# PMS.net
KiCad netlist of a schematic drawn in Altium Designer
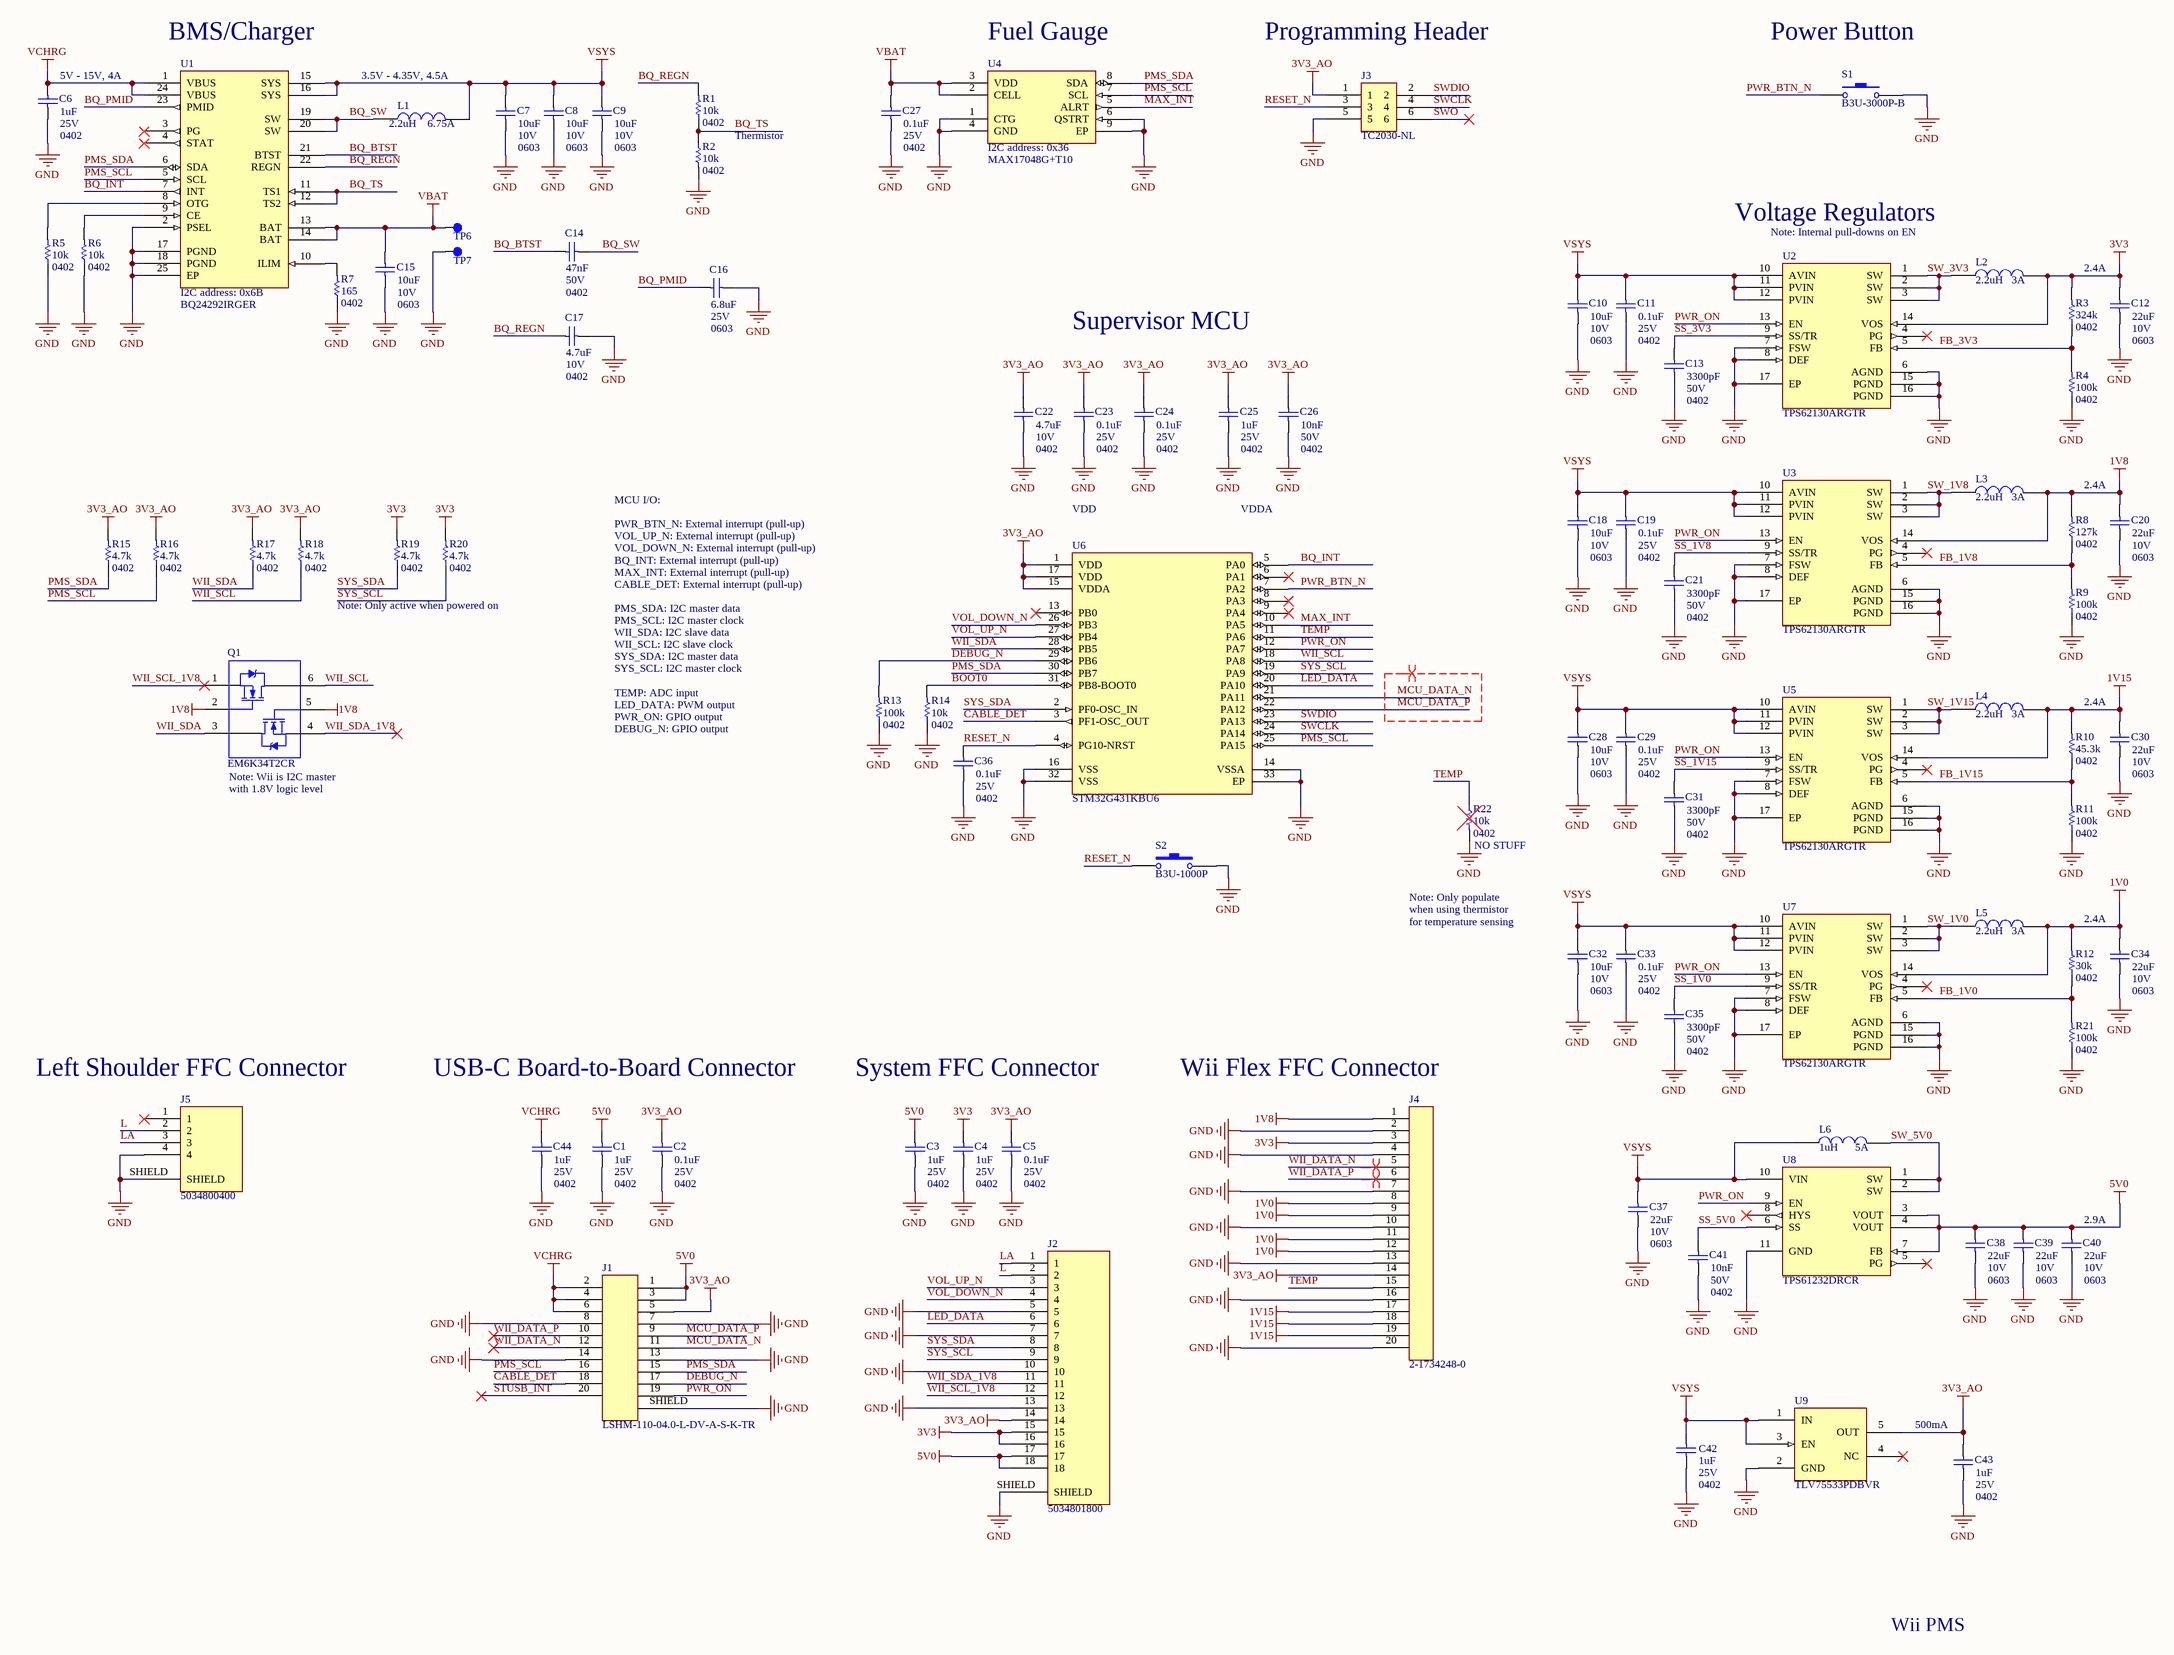
[diagram p0: PMS.SchDoc]

(export (version "E")
  (design (tool "Eeschema 10.0.6"))
  (components
    (comp (ref "C1")
      (value "1uF")
      (footprint "CAPC1005X06N")
      (description "General purpose capacitor")
      (fields
        (field (name "RATED VOLTAGE") "25V")
        (field (name "PACKAGE") "0402")
        (field (name "Comment") "Capacitor")
      )
      (libsource (lib "Schematic_Generic") (part "Capacitor"))
    )
    (comp (ref "C2")
      (value "0.1uF")
      (footprint "CAPC1005X06N")
      (description "General purpose capacitor")
      (fields
        (field (name "RATED VOLTAGE") "25V")
        (field (name "PACKAGE") "0402")
        (field (name "Comment") "Capacitor")
      )
      (libsource (lib "Schematic_Generic") (part "Capacitor"))
    )
    (comp (ref "C3")
      (value "1uF")
      (footprint "CAPC1005X06N")
      (description "General purpose capacitor")
      (fields
        (field (name "RATED VOLTAGE") "25V")
        (field (name "PACKAGE") "0402")
        (field (name "Comment") "Capacitor")
      )
      (libsource (lib "Schematic_Generic") (part "Capacitor"))
    )
    (comp (ref "C4")
      (value "1uF")
      (footprint "CAPC1005X06N")
      (description "General purpose capacitor")
      (fields
        (field (name "RATED VOLTAGE") "25V")
        (field (name "PACKAGE") "0402")
        (field (name "Comment") "Capacitor")
      )
      (libsource (lib "Schematic_Generic") (part "Capacitor"))
    )
    (comp (ref "C5")
      (value "0.1uF")
      (footprint "CAPC1005X06N")
      (description "General purpose capacitor")
      (fields
        (field (name "RATED VOLTAGE") "25V")
        (field (name "PACKAGE") "0402")
        (field (name "Comment") "Capacitor")
      )
      (libsource (lib "Schematic_Generic") (part "Capacitor"))
    )
    (comp (ref "C6")
      (value "1uF")
      (footprint "CAPC1005X06N")
      (description "General purpose capacitor")
      (fields
        (field (name "RATED VOLTAGE") "25V")
        (field (name "PACKAGE") "0402")
        (field (name "Comment") "Capacitor")
      )
      (libsource (lib "Schematic_Generic") (part "Capacitor"))
    )
    (comp (ref "C7")
      (value "10uF")
      (footprint "CAPC1608X09N")
      (description "General purpose capacitor")
      (fields
        (field (name "RATED VOLTAGE") "10V")
        (field (name "PACKAGE") "0603")
        (field (name "Comment") "Capacitor")
      )
      (libsource (lib "Schematic_Generic") (part "Capacitor"))
    )
    (comp (ref "C8")
      (value "10uF")
      (footprint "CAPC1608X09N")
      (description "General purpose capacitor")
      (fields
        (field (name "RATED VOLTAGE") "10V")
        (field (name "PACKAGE") "0603")
        (field (name "Comment") "Capacitor")
      )
      (libsource (lib "Schematic_Generic") (part "Capacitor"))
    )
    (comp (ref "C9")
      (value "10uF")
      (footprint "CAPC1608X09N")
      (description "General purpose capacitor")
      (fields
        (field (name "RATED VOLTAGE") "10V")
        (field (name "PACKAGE") "0603")
        (field (name "Comment") "Capacitor")
      )
      (libsource (lib "Schematic_Generic") (part "Capacitor"))
    )
    (comp (ref "C10")
      (value "10uF")
      (footprint "CAPC1608X09N")
      (description "General purpose capacitor")
      (fields
        (field (name "RATED VOLTAGE") "10V")
        (field (name "PACKAGE") "0603")
        (field (name "Comment") "Capacitor")
      )
      (libsource (lib "Schematic_Generic") (part "Capacitor"))
    )
    (comp (ref "C11")
      (value "0.1uF")
      (footprint "CAPC1005X06N")
      (description "General purpose capacitor")
      (fields
        (field (name "RATED VOLTAGE") "25V")
        (field (name "PACKAGE") "0402")
        (field (name "Comment") "Capacitor")
      )
      (libsource (lib "Schematic_Generic") (part "Capacitor"))
    )
    (comp (ref "C12")
      (value "22uF")
      (footprint "CAPC1608X09N")
      (description "General purpose capacitor")
      (fields
        (field (name "RATED VOLTAGE") "10V")
        (field (name "PACKAGE") "0603")
        (field (name "Comment") "Capacitor")
      )
      (libsource (lib "Schematic_Generic") (part "Capacitor"))
    )
    (comp (ref "C13")
      (value "3300pF")
      (footprint "CAPC1005X06N")
      (description "General purpose capacitor")
      (fields
        (field (name "RATED VOLTAGE") "50V")
        (field (name "PACKAGE") "0402")
        (field (name "Comment") "Capacitor")
      )
      (libsource (lib "Schematic_Generic") (part "Capacitor"))
    )
    (comp (ref "C14")
      (value "47nF")
      (footprint "CAPC1005X06N")
      (description "General purpose capacitor")
      (fields
        (field (name "RATED VOLTAGE") "50V")
        (field (name "PACKAGE") "0402")
        (field (name "Comment") "Capacitor")
      )
      (libsource (lib "Schematic_Generic") (part "Capacitor"))
    )
    (comp (ref "C15")
      (value "10uF")
      (footprint "CAPC1608X09N")
      (description "General purpose capacitor")
      (fields
        (field (name "RATED VOLTAGE") "10V")
        (field (name "PACKAGE") "0603")
        (field (name "Comment") "Capacitor")
      )
      (libsource (lib "Schematic_Generic") (part "Capacitor"))
    )
    (comp (ref "C16")
      (value "6.8uF")
      (footprint "CAPC1608X09N")
      (description "General purpose capacitor")
      (fields
        (field (name "RATED VOLTAGE") "25V")
        (field (name "PACKAGE") "0603")
        (field (name "Comment") "Capacitor")
      )
      (libsource (lib "Schematic_Generic") (part "Capacitor"))
    )
    (comp (ref "C17")
      (value "4.7uF")
      (footprint "CAPC1005X06N")
      (description "General purpose capacitor")
      (fields
        (field (name "RATED VOLTAGE") "10V")
        (field (name "PACKAGE") "0402")
        (field (name "Comment") "Capacitor")
      )
      (libsource (lib "Schematic_Generic") (part "Capacitor"))
    )
    (comp (ref "C18")
      (value "10uF")
      (footprint "CAPC1608X09N")
      (description "General purpose capacitor")
      (fields
        (field (name "RATED VOLTAGE") "10V")
        (field (name "PACKAGE") "0603")
        (field (name "Comment") "Capacitor")
      )
      (libsource (lib "Schematic_Generic") (part "Capacitor"))
    )
    (comp (ref "C19")
      (value "0.1uF")
      (footprint "CAPC1005X06N")
      (description "General purpose capacitor")
      (fields
        (field (name "RATED VOLTAGE") "25V")
        (field (name "PACKAGE") "0402")
        (field (name "Comment") "Capacitor")
      )
      (libsource (lib "Schematic_Generic") (part "Capacitor"))
    )
    (comp (ref "C20")
      (value "22uF")
      (footprint "CAPC1608X09N")
      (description "General purpose capacitor")
      (fields
        (field (name "RATED VOLTAGE") "10V")
        (field (name "PACKAGE") "0603")
        (field (name "Comment") "Capacitor")
      )
      (libsource (lib "Schematic_Generic") (part "Capacitor"))
    )
    (comp (ref "C21")
      (value "3300pF")
      (footprint "CAPC1005X06N")
      (description "General purpose capacitor")
      (fields
        (field (name "RATED VOLTAGE") "50V")
        (field (name "PACKAGE") "0402")
        (field (name "Comment") "Capacitor")
      )
      (libsource (lib "Schematic_Generic") (part "Capacitor"))
    )
    (comp (ref "C22")
      (value "4.7uF")
      (footprint "CAPC1005X06N")
      (description "General purpose capacitor")
      (fields
        (field (name "RATED VOLTAGE") "10V")
        (field (name "PACKAGE") "0402")
        (field (name "Comment") "Capacitor")
      )
      (libsource (lib "Schematic_Generic") (part "Capacitor"))
    )
    (comp (ref "C23")
      (value "0.1uF")
      (footprint "CAPC1005X06N")
      (description "General purpose capacitor")
      (fields
        (field (name "RATED VOLTAGE") "25V")
        (field (name "PACKAGE") "0402")
        (field (name "Comment") "Capacitor")
      )
      (libsource (lib "Schematic_Generic") (part "Capacitor"))
    )
    (comp (ref "C24")
      (value "0.1uF")
      (footprint "CAPC1005X06N")
      (description "General purpose capacitor")
      (fields
        (field (name "RATED VOLTAGE") "25V")
        (field (name "PACKAGE") "0402")
        (field (name "Comment") "Capacitor")
      )
      (libsource (lib "Schematic_Generic") (part "Capacitor"))
    )
    (comp (ref "C25")
      (value "1uF")
      (footprint "CAPC1005X06N")
      (description "General purpose capacitor")
      (fields
        (field (name "RATED VOLTAGE") "25V")
        (field (name "PACKAGE") "0402")
        (field (name "Comment") "Capacitor")
      )
      (libsource (lib "Schematic_Generic") (part "Capacitor"))
    )
    (comp (ref "C26")
      (value "10nF")
      (footprint "CAPC1005X06N")
      (description "General purpose capacitor")
      (fields
        (field (name "RATED VOLTAGE") "50V")
        (field (name "PACKAGE") "0402")
        (field (name "Comment") "Capacitor")
      )
      (libsource (lib "Schematic_Generic") (part "Capacitor"))
    )
    (comp (ref "C27")
      (value "0.1uF")
      (footprint "CAPC1005X06N")
      (description "General purpose capacitor")
      (fields
        (field (name "RATED VOLTAGE") "25V")
        (field (name "PACKAGE") "0402")
        (field (name "Comment") "Capacitor")
      )
      (libsource (lib "Schematic_Generic") (part "Capacitor"))
    )
    (comp (ref "C28")
      (value "10uF")
      (footprint "CAPC1608X09N")
      (description "General purpose capacitor")
      (fields
        (field (name "RATED VOLTAGE") "10V")
        (field (name "PACKAGE") "0603")
        (field (name "Comment") "Capacitor")
      )
      (libsource (lib "Schematic_Generic") (part "Capacitor"))
    )
    (comp (ref "C29")
      (value "0.1uF")
      (footprint "CAPC1005X06N")
      (description "General purpose capacitor")
      (fields
        (field (name "RATED VOLTAGE") "25V")
        (field (name "PACKAGE") "0402")
        (field (name "Comment") "Capacitor")
      )
      (libsource (lib "Schematic_Generic") (part "Capacitor"))
    )
    (comp (ref "C30")
      (value "22uF")
      (footprint "CAPC1608X09N")
      (description "General purpose capacitor")
      (fields
        (field (name "RATED VOLTAGE") "10V")
        (field (name "PACKAGE") "0603")
        (field (name "Comment") "Capacitor")
      )
      (libsource (lib "Schematic_Generic") (part "Capacitor"))
    )
    (comp (ref "C31")
      (value "3300pF")
      (footprint "CAPC1005X06N")
      (description "General purpose capacitor")
      (fields
        (field (name "RATED VOLTAGE") "50V")
        (field (name "PACKAGE") "0402")
        (field (name "Comment") "Capacitor")
      )
      (libsource (lib "Schematic_Generic") (part "Capacitor"))
    )
    (comp (ref "C32")
      (value "10uF")
      (footprint "CAPC1608X09N")
      (description "General purpose capacitor")
      (fields
        (field (name "RATED VOLTAGE") "10V")
        (field (name "PACKAGE") "0603")
        (field (name "Comment") "Capacitor")
      )
      (libsource (lib "Schematic_Generic") (part "Capacitor"))
    )
    (comp (ref "C33")
      (value "0.1uF")
      (footprint "CAPC1005X06N")
      (description "General purpose capacitor")
      (fields
        (field (name "RATED VOLTAGE") "25V")
        (field (name "PACKAGE") "0402")
        (field (name "Comment") "Capacitor")
      )
      (libsource (lib "Schematic_Generic") (part "Capacitor"))
    )
    (comp (ref "C34")
      (value "22uF")
      (footprint "CAPC1608X09N")
      (description "General purpose capacitor")
      (fields
        (field (name "RATED VOLTAGE") "10V")
        (field (name "PACKAGE") "0603")
        (field (name "Comment") "Capacitor")
      )
      (libsource (lib "Schematic_Generic") (part "Capacitor"))
    )
    (comp (ref "C35")
      (value "3300pF")
      (footprint "CAPC1005X06N")
      (description "General purpose capacitor")
      (fields
        (field (name "RATED VOLTAGE") "50V")
        (field (name "PACKAGE") "0402")
        (field (name "Comment") "Capacitor")
      )
      (libsource (lib "Schematic_Generic") (part "Capacitor"))
    )
    (comp (ref "C36")
      (value "0.1uF")
      (footprint "CAPC1005X06N")
      (description "General purpose capacitor")
      (fields
        (field (name "RATED VOLTAGE") "25V")
        (field (name "PACKAGE") "0402")
        (field (name "Comment") "Capacitor")
      )
      (libsource (lib "Schematic_Generic") (part "Capacitor"))
    )
    (comp (ref "C37")
      (value "22uF")
      (footprint "CAPC1608X09N")
      (description "General purpose capacitor")
      (fields
        (field (name "RATED VOLTAGE") "10V")
        (field (name "PACKAGE") "0603")
        (field (name "Comment") "Capacitor")
      )
      (libsource (lib "Schematic_Generic") (part "Capacitor"))
    )
    (comp (ref "C38")
      (value "22uF")
      (footprint "CAPC1608X09N")
      (description "General purpose capacitor")
      (fields
        (field (name "RATED VOLTAGE") "10V")
        (field (name "PACKAGE") "0603")
        (field (name "Comment") "Capacitor")
      )
      (libsource (lib "Schematic_Generic") (part "Capacitor"))
    )
    (comp (ref "C39")
      (value "22uF")
      (footprint "CAPC1608X09N")
      (description "General purpose capacitor")
      (fields
        (field (name "RATED VOLTAGE") "10V")
        (field (name "PACKAGE") "0603")
        (field (name "Comment") "Capacitor")
      )
      (libsource (lib "Schematic_Generic") (part "Capacitor"))
    )
    (comp (ref "C40")
      (value "22uF")
      (footprint "CAPC1608X09N")
      (description "General purpose capacitor")
      (fields
        (field (name "RATED VOLTAGE") "10V")
        (field (name "PACKAGE") "0603")
        (field (name "Comment") "Capacitor")
      )
      (libsource (lib "Schematic_Generic") (part "Capacitor"))
    )
    (comp (ref "C41")
      (value "10nF")
      (footprint "CAPC1005X06N")
      (description "General purpose capacitor")
      (fields
        (field (name "RATED VOLTAGE") "50V")
        (field (name "PACKAGE") "0402")
        (field (name "Comment") "Capacitor")
      )
      (libsource (lib "Schematic_Generic") (part "Capacitor"))
    )
    (comp (ref "C42")
      (value "1uF")
      (footprint "CAPC1005X06N")
      (description "General purpose capacitor")
      (fields
        (field (name "RATED VOLTAGE") "25V")
        (field (name "PACKAGE") "0402")
        (field (name "Comment") "Capacitor")
      )
      (libsource (lib "Schematic_Generic") (part "Capacitor"))
    )
    (comp (ref "C43")
      (value "1uF")
      (footprint "CAPC1005X06N")
      (description "General purpose capacitor")
      (fields
        (field (name "RATED VOLTAGE") "25V")
        (field (name "PACKAGE") "0402")
        (field (name "Comment") "Capacitor")
      )
      (libsource (lib "Schematic_Generic") (part "Capacitor"))
    )
    (comp (ref "C44")
      (value "1uF")
      (footprint "CAPC1005X06N")
      (description "General purpose capacitor")
      (fields
        (field (name "RATED VOLTAGE") "25V")
        (field (name "PACKAGE") "0402")
        (field (name "Comment") "Capacitor")
      )
      (libsource (lib "Schematic_Generic") (part "Capacitor"))
    )
    (comp (ref "J1")
      (value "LSHM-110-04.0-L-DV-A-S-K-TR")
      (footprint "Footprint_Connector:LSHM-110-04.0-L-DV-A-S")
      (description "HERMAPHRODITIC 0.50MM SMD 20POS 4MM")
      (fields (field (name "MANUFACTURER") "Samtec"))
      (libsource (lib "Schematic_Connector") (part "LSHM-110-04.0-L-DV-A-S-K-TR"))
    )
    (comp (ref "J2")
      (value "5034801800")
      (footprint "Footprint_Connector:5034801800")
      (description "CONN FFC FPC 18POS 0.50MM R/A")
      (fields (field (name "MANUFACTURER") "Molex"))
      (libsource (lib "Schematic_Connector") (part "5034801800"))
    )
    (comp (ref "J3")
      (value "TC2030-NL")
      (footprint "Footprint_Connector:TC2030-NL")
      (description "6-Pin No-Legs Tag-Connect Plug-of-Nails™ Cable with Ribbon Connector")
      (libsource (lib "Schematic_Connector") (part "TC2030-NL"))
    )
    (comp (ref "J4")
      (value "2-1734248-0")
      (footprint "Footprint_Connector:2-1734248-0")
      (description "FFC/FPC CONNECTOR, RECEPTACLE 20POS 1ROW")
      (fields (field (name "MANUFACTURER") "TE Connectivity"))
      (libsource (lib "Schematic_Connector") (part "2-1734248-0"))
    )
    (comp (ref "J5")
      (value "5034800400")
      (footprint "Footprint_Connector:5034800400")
      (description "CONN FFC FPC 4POS 0.50MM R/A")
      (fields (field (name "MANUFACTURER") "Molex"))
      (libsource (lib "Schematic_Connector") (part "5034800400"))
    )
    (comp (ref "L1")
      (value "IHLP2020CZER2R2M11")
      (footprint "Footprint_Inductor:INDM5252X30N")
      (description "FIXED IND 2.2UH 6.75A 25 MOHM")
      (fields
        (field (name "MANUFACTURER") "Vishay Dale")
        (field (name "TOLERANCE") "20%")
        (field (name "CURRENT RATING") "6.75A")
        (field (name "INDUCTANCE") "2.2uH")
      )
      (libsource (lib "Schematic_Inductor") (part "IHLP2020CZER2R2M11"))
    )
    (comp (ref "L2")
      (value "IHLP1212BZER2R2M11")
      (footprint "Footprint_Inductor:INDM3030X20N")
      (description "FIXED IND 2.2UH 3A 46 MOHM SMD")
      (fields
        (field (name "MANUFACTURER") "Vishay Dale")
        (field (name "TOLERANCE") "20%")
        (field (name "CURRENT RATING") "3A")
        (field (name "INDUCTANCE") "2.2uH")
      )
      (libsource (lib "Schematic_Inductor") (part "IHLP1212BZER2R2M11"))
    )
    (comp (ref "L3")
      (value "IHLP1212BZER2R2M11")
      (footprint "Footprint_Inductor:INDM3030X20N")
      (description "FIXED IND 2.2UH 3A 46 MOHM SMD")
      (fields
        (field (name "MANUFACTURER") "Vishay Dale")
        (field (name "TOLERANCE") "20%")
        (field (name "CURRENT RATING") "3A")
        (field (name "INDUCTANCE") "2.2uH")
      )
      (libsource (lib "Schematic_Inductor") (part "IHLP1212BZER2R2M11"))
    )
    (comp (ref "L4")
      (value "IHLP1212BZER2R2M11")
      (footprint "Footprint_Inductor:INDM3030X20N")
      (description "FIXED IND 2.2UH 3A 46 MOHM SMD")
      (fields
        (field (name "MANUFACTURER") "Vishay Dale")
        (field (name "TOLERANCE") "20%")
        (field (name "CURRENT RATING") "3A")
        (field (name "INDUCTANCE") "2.2uH")
      )
      (libsource (lib "Schematic_Inductor") (part "IHLP1212BZER2R2M11"))
    )
    (comp (ref "L5")
      (value "IHLP1212BZER2R2M11")
      (footprint "Footprint_Inductor:INDM3030X20N")
      (description "FIXED IND 2.2UH 3A 46 MOHM SMD")
      (fields
        (field (name "MANUFACTURER") "Vishay Dale")
        (field (name "TOLERANCE") "20%")
        (field (name "CURRENT RATING") "3A")
        (field (name "INDUCTANCE") "2.2uH")
      )
      (libsource (lib "Schematic_Inductor") (part "IHLP1212BZER2R2M11"))
    )
    (comp (ref "L6")
      (value "IHLP1212BZER1R0M11")
      (footprint "Footprint_Inductor:INDM3030X20N")
      (description "FIXED IND 1UH 5A 24 MOHM SMD")
      (fields
        (field (name "MANUFACTURER") "Vishay Dale")
        (field (name "TOLERANCE") "20%")
        (field (name "INDUCTANCE") "1uH")
        (field (name "CURRENT RATING") "5A")
      )
      (libsource (lib "Schematic_Inductor") (part "IHLP1212BZER1R0M11"))
    )
    (comp (ref "Q1")
      (value "EM6K34T2CR")
      (footprint "Footprint_Transistor:SOTFL50P160X50-6N")
      (description "MOSFET 2N-CH 50V 0.2A EMT6")
      (fields (field (name "MANUFACTURER") "Rohm"))
      (libsource (lib "Schematic_Transistor") (part "EM6K34T2CR"))
    )
    (comp (ref "R1")
      (value "10k")
      (footprint "RESC1005X04N")
      (description "General purpose resistor")
      (fields (field (name "PACKAGE") "0402") (field (name "Comment") "Resistor"))
      (libsource (lib "Schematic_Generic") (part "Resistor"))
    )
    (comp (ref "R2")
      (value "10k")
      (footprint "RESC1005X04N")
      (description "General purpose resistor")
      (fields (field (name "PACKAGE") "0402") (field (name "Comment") "Resistor"))
      (libsource (lib "Schematic_Generic") (part "Resistor"))
    )
    (comp (ref "R3")
      (value "324k")
      (footprint "RESC1005X04N")
      (description "General purpose resistor")
      (fields (field (name "PACKAGE") "0402") (field (name "Comment") "Resistor"))
      (libsource (lib "Schematic_Generic") (part "Resistor"))
    )
    (comp (ref "R4")
      (value "100k")
      (footprint "RESC1005X04N")
      (description "General purpose resistor")
      (fields (field (name "PACKAGE") "0402") (field (name "Comment") "Resistor"))
      (libsource (lib "Schematic_Generic") (part "Resistor"))
    )
    (comp (ref "R5")
      (value "10k")
      (footprint "RESC1005X04N")
      (description "General purpose resistor")
      (fields (field (name "PACKAGE") "0402") (field (name "Comment") "Resistor"))
      (libsource (lib "Schematic_Generic") (part "Resistor"))
    )
    (comp (ref "R6")
      (value "10k")
      (footprint "RESC1005X04N")
      (description "General purpose resistor")
      (fields (field (name "PACKAGE") "0402") (field (name "Comment") "Resistor"))
      (libsource (lib "Schematic_Generic") (part "Resistor"))
    )
    (comp (ref "R7")
      (value "165")
      (footprint "RESC1005X04N")
      (description "General purpose resistor")
      (fields (field (name "PACKAGE") "0402") (field (name "Comment") "Resistor"))
      (libsource (lib "Schematic_Generic") (part "Resistor"))
    )
    (comp (ref "R8")
      (value "127k")
      (footprint "RESC1005X04N")
      (description "General purpose resistor")
      (fields (field (name "PACKAGE") "0402") (field (name "Comment") "Resistor"))
      (libsource (lib "Schematic_Generic") (part "Resistor"))
    )
    (comp (ref "R9")
      (value "100k")
      (footprint "RESC1005X04N")
      (description "General purpose resistor")
      (fields (field (name "PACKAGE") "0402") (field (name "Comment") "Resistor"))
      (libsource (lib "Schematic_Generic") (part "Resistor"))
    )
    (comp (ref "R10")
      (value "45.3k")
      (footprint "RESC1005X04N")
      (description "General purpose resistor")
      (fields (field (name "PACKAGE") "0402") (field (name "Comment") "Resistor"))
      (libsource (lib "Schematic_Generic") (part "Resistor"))
    )
    (comp (ref "R11")
      (value "100k")
      (footprint "RESC1005X04N")
      (description "General purpose resistor")
      (fields (field (name "PACKAGE") "0402") (field (name "Comment") "Resistor"))
      (libsource (lib "Schematic_Generic") (part "Resistor"))
    )
    (comp (ref "R12")
      (value "30k")
      (footprint "RESC1005X04N")
      (description "General purpose resistor")
      (fields (field (name "PACKAGE") "0402") (field (name "Comment") "Resistor"))
      (libsource (lib "Schematic_Generic") (part "Resistor"))
    )
    (comp (ref "R13")
      (value "100k")
      (footprint "RESC1005X04N")
      (description "General purpose resistor")
      (fields (field (name "PACKAGE") "0402") (field (name "Comment") "Resistor"))
      (libsource (lib "Schematic_Generic") (part "Resistor"))
    )
    (comp (ref "R14")
      (value "10k")
      (footprint "RESC1005X04N")
      (description "General purpose resistor")
      (fields (field (name "PACKAGE") "0402") (field (name "Comment") "Resistor"))
      (libsource (lib "Schematic_Generic") (part "Resistor"))
    )
    (comp (ref "R15")
      (value "4.7k")
      (footprint "RESC1005X04N")
      (description "General purpose resistor")
      (fields (field (name "PACKAGE") "0402") (field (name "Comment") "Resistor"))
      (libsource (lib "Schematic_Generic") (part "Resistor"))
    )
    (comp (ref "R16")
      (value "4.7k")
      (footprint "RESC1005X04N")
      (description "General purpose resistor")
      (fields (field (name "PACKAGE") "0402") (field (name "Comment") "Resistor"))
      (libsource (lib "Schematic_Generic") (part "Resistor"))
    )
    (comp (ref "R17")
      (value "4.7k")
      (footprint "RESC1005X04N")
      (description "General purpose resistor")
      (fields (field (name "PACKAGE") "0402") (field (name "Comment") "Resistor"))
      (libsource (lib "Schematic_Generic") (part "Resistor"))
    )
    (comp (ref "R18")
      (value "4.7k")
      (footprint "RESC1005X04N")
      (description "General purpose resistor")
      (fields (field (name "PACKAGE") "0402") (field (name "Comment") "Resistor"))
      (libsource (lib "Schematic_Generic") (part "Resistor"))
    )
    (comp (ref "R19")
      (value "4.7k")
      (footprint "RESC1005X04N")
      (description "General purpose resistor")
      (fields (field (name "PACKAGE") "0402") (field (name "Comment") "Resistor"))
      (libsource (lib "Schematic_Generic") (part "Resistor"))
    )
    (comp (ref "R20")
      (value "4.7k")
      (footprint "RESC1005X04N")
      (description "General purpose resistor")
      (fields (field (name "PACKAGE") "0402") (field (name "Comment") "Resistor"))
      (libsource (lib "Schematic_Generic") (part "Resistor"))
    )
    (comp (ref "R21")
      (value "100k")
      (footprint "RESC1005X04N")
      (description "General purpose resistor")
      (fields (field (name "PACKAGE") "0402") (field (name "Comment") "Resistor"))
      (libsource (lib "Schematic_Generic") (part "Resistor"))
    )
    (comp (ref "R22")
      (value "10k")
      (footprint "RESC1005X04N")
      (description "General purpose resistor")
      (fields
        (field (name "PACKAGE") "0402")
        (field (name "NOTE") "NO STUFF")
        (field (name "Comment") "Resistor")
      )
      (libsource (lib "Schematic_Generic") (part "Resistor"))
    )
    (comp (ref "S1")
      (value "B3U-3000P-B")
      (footprint "Footprint_Button:B3U-3000P-B")
      (description "Switch Tactile N.O. SPST Button Gull Wing 0.05A 12VDC 1.59N SMD Embossed T/R")
      (fields (field (name "MANUFACTURER") "Omron"))
      (libsource (lib "Schematic_Button") (part "B3U-3000P-B"))
    )
    (comp (ref "S2")
      (value "B3U-1000P")
      (footprint "Footprint_Button:B3U-1000P")
      (description "OMRON ELECTRONIC COMPONENTS         B3U-1000P            SWITCH, SPST-NO, 0.05A, 12V, SMD")
      (fields (field (name "MANUFACTURER") "Omron"))
      (libsource (lib "Schematic_Button") (part "B3U-1000P"))
    )
    (comp (ref "TP6")
      (value "Test Point")
      (footprint "Footprint_Testpoint:TP_RECTANGULAR_1.5X2MM")
      (description "General purpose test point")
      (libsource (lib "Schematic_Generic") (part "Test Point"))
    )
    (comp (ref "TP7")
      (value "Test Point")
      (footprint "Footprint_Testpoint:TP_RECTANGULAR_1.5X2MM")
      (description "General purpose test point")
      (libsource (lib "Schematic_Generic") (part "Test Point"))
    )
    (comp (ref "U1")
      (value "BQ24292IRGER")
      (footprint "Footprint_PMIC:QFN50P400X400X100_HS-25N")
      (description "IC LI+ CHARGER PWR MGMT 24VQFN")
      (fields (field (name "MANUFACTURER") "Texas Instruments"))
      (libsource (lib "Schematic_PMIC") (part "BQ24292IRGER"))
    )
    (comp (ref "U2")
      (value "TPS62130ARGTR")
      (footprint "Footprint_PMIC:QFN50P300X300X100_HS-17N")
      (description "Conv DC-DC Single Step Down 3V to 17V 16-Pin QFN T/R")
      (fields (field (name "MANUFACTURER") "Texas Instruments"))
      (libsource (lib "Schematic_PMIC") (part "TPS62130ARGTR"))
    )
    (comp (ref "U3")
      (value "TPS62130ARGTR")
      (footprint "Footprint_PMIC:QFN50P300X300X100_HS-17N")
      (description "Conv DC-DC Single Step Down 3V to 17V 16-Pin QFN T/R")
      (fields (field (name "MANUFACTURER") "Texas Instruments"))
      (libsource (lib "Schematic_PMIC") (part "TPS62130ARGTR"))
    )
    (comp (ref "U4")
      (value "MAX17048G+T10")
      (footprint "Footprint_IC:SON50P200X80_HS-9N")
      (description "IC FUEL GAUGE LI-ION 1CELL 8TDFN")
      (fields (field (name "MANUFACTURER") "Maxim"))
      (libsource (lib "Schematic_IC") (part "MAX17048G+T10"))
    )
    (comp (ref "U5")
      (value "TPS62130ARGTR")
      (footprint "Footprint_PMIC:QFN50P300X300X100_HS-17N")
      (description "Conv DC-DC Single Step Down 3V to 17V 16-Pin QFN T/R")
      (fields (field (name "MANUFACTURER") "Texas Instruments"))
      (libsource (lib "Schematic_PMIC") (part "TPS62130ARGTR"))
    )
    (comp (ref "U6")
      (value "STM32G431KBU6")
      (footprint "Footprint_MCU:QFN50P500X500X60_HS-33N")
      (description "MCU 32-Bit ARM Cortex-M4 RISC 128KB Flash 1.71V to 3.6V 32-Pin UFQFPN")
      (fields (field (name "MANUFACTURER") "STMicroelectronics"))
      (libsource (lib "Schematic_MCU") (part "STM32G431KBU6"))
    )
    (comp (ref "U7")
      (value "TPS62130ARGTR")
      (footprint "Footprint_PMIC:QFN50P300X300X100_HS-17N")
      (description "Conv DC-DC Single Step Down 3V to 17V 16-Pin QFN T/R")
      (fields (field (name "MANUFACTURER") "Texas Instruments"))
      (libsource (lib "Schematic_PMIC") (part "TPS62130ARGTR"))
    )
    (comp (ref "U8")
      (value "TPS61232DRCR")
      (footprint "Footprint_PMIC:SON50P300X100_HS-11N")
      (description "IC REG BOOST 5V 4A 10VSON")
      (fields (field (name "MANUFACTURER") "Texas Instruments"))
      (libsource (lib "Schematic_PMIC") (part "TPS61232DRCR"))
    )
    (comp (ref "U9")
      (value "TLV75533PDBVR")
      (footprint "Footprint_PMIC:SOT95P280X145-5N")
      (description "IC REG LINEAR 3.3V 500MA SOT23-5")
      (fields (field (name "MANUFACTURER") "Texas Instruments"))
      (libsource (lib "Schematic_PMIC") (part "TLV75533PDBVR"))
    )
  )
  (nets
    (net (code "1") (name "/BOOT0") (class "Default")
      (node (ref "R14") (pin "2") (pinfunction "2_2") (pintype "passive"))
      (node (ref "U6") (pin "31") (pinfunction "PB8-BOOT0_31") (pintype "bidirectional"))
    )
    (net (code "2") (name "/BQ_BTST") (class "Default")
      (node (ref "C14") (pin "1") (pinfunction "1_1") (pintype "passive"))
      (node (ref "U1") (pin "21") (pinfunction "BTST_21") (pintype "power_in"))
    )
    (net (code "3") (name "/BQ_INT") (class "Default")
      (node (ref "U1") (pin "7") (pinfunction "INT_7") (pintype "output"))
      (node (ref "U6") (pin "5") (pinfunction "PA0_5") (pintype "bidirectional"))
    )
    (net (code "4") (name "/BQ_PMID") (class "Default")
      (node (ref "C16") (pin "1") (pinfunction "1_1") (pintype "passive"))
      (node (ref "U1") (pin "23") (pinfunction "PMID_23") (pintype "output"))
    )
    (net (code "5") (name "/BQ_REGN") (class "Default")
      (node (ref "C17") (pin "1") (pinfunction "1_1") (pintype "passive"))
      (node (ref "R1") (pin "2") (pinfunction "2_2") (pintype "passive"))
      (node (ref "U1") (pin "22") (pinfunction "REGN_22") (pintype "power_in"))
    )
    (net (code "6") (name "/BQ_SW") (class "Default")
      (node (ref "C14") (pin "2") (pinfunction "2_2") (pintype "passive"))
      (node (ref "L1") (pin "1") (pinfunction "1_1") (pintype "passive"))
      (node (ref "U1") (pin "19") (pinfunction "SW_19") (pintype "power_in"))
      (node (ref "U1") (pin "20") (pinfunction "SW_20") (pintype "power_in"))
    )
    (net (code "7") (name "/BQ_TS") (class "Default")
      (node (ref "R1") (pin "1") (pinfunction "1_1") (pintype "passive"))
      (node (ref "R2") (pin "1") (pinfunction "1_1") (pintype "passive"))
      (node (ref "U1") (pin "11") (pinfunction "TS1_11") (pintype "input"))
      (node (ref "U1") (pin "12") (pinfunction "TS2_12") (pintype "input"))
    )
    (net (code "8") (name "/CABLE_DET") (class "Default")
      (node (ref "J1") (pin "18") (pintype "passive"))
      (node (ref "U6") (pin "3") (pinfunction "PF1-OSC_OUT_3") (pintype "output"))
    )
    (net (code "9") (name "/DEBUG_N") (class "Default")
      (node (ref "J1") (pin "17") (pintype "passive"))
      (node (ref "R13") (pin "2") (pinfunction "2_2") (pintype "passive"))
      (node (ref "U6") (pin "29") (pinfunction "PB6_29") (pintype "bidirectional"))
    )
    (net (code "10") (name "/FB_1V0") (class "Default")
      (node (ref "R12") (pin "1") (pinfunction "1_1") (pintype "passive"))
      (node (ref "R21") (pin "2") (pinfunction "2_2") (pintype "passive"))
      (node (ref "U7") (pin "5") (pinfunction "FB_5") (pintype "input"))
    )
    (net (code "11") (name "/FB_1V8") (class "Default")
      (node (ref "R8") (pin "1") (pinfunction "1_1") (pintype "passive"))
      (node (ref "R9") (pin "2") (pinfunction "2_2") (pintype "passive"))
      (node (ref "U3") (pin "5") (pinfunction "FB_5") (pintype "input"))
    )
    (net (code "12") (name "/FB_1V15") (class "Default")
      (node (ref "R10") (pin "1") (pinfunction "1_1") (pintype "passive"))
      (node (ref "R11") (pin "2") (pinfunction "2_2") (pintype "passive"))
      (node (ref "U5") (pin "5") (pinfunction "FB_5") (pintype "input"))
    )
    (net (code "13") (name "/FB_3V3") (class "Default")
      (node (ref "R3") (pin "1") (pinfunction "1_1") (pintype "passive"))
      (node (ref "R4") (pin "2") (pinfunction "2_2") (pintype "passive"))
      (node (ref "U2") (pin "5") (pinfunction "FB_5") (pintype "input"))
    )
    (net (code "14") (name "/L") (class "Default")
      (node (ref "J2") (pin "2") (pinfunction "2_2") (pintype "passive"))
      (node (ref "J5") (pin "2") (pinfunction "2_2") (pintype "passive"))
    )
    (net (code "15") (name "/LA") (class "Default")
      (node (ref "J2") (pin "1") (pinfunction "1_1") (pintype "passive"))
      (node (ref "J5") (pin "3") (pinfunction "3_3") (pintype "passive"))
    )
    (net (code "16") (name "/LED_DATA") (class "Default")
      (node (ref "J2") (pin "6") (pinfunction "6_6") (pintype "passive"))
      (node (ref "U6") (pin "20") (pinfunction "PA10_20") (pintype "bidirectional"))
    )
    (net (code "17") (name "/MAX_INT") (class "Default")
      (node (ref "U4") (pin "5") (pinfunction "ALRT_5") (pintype "output"))
      (node (ref "U6") (pin "10") (pinfunction "PA5_10") (pintype "bidirectional"))
    )
    (net (code "18") (name "/MCU_DATA_N") (class "Default")
      (node (ref "J1") (pin "11") (pintype "passive"))
      (node (ref "U6") (pin "21") (pinfunction "PA11_21") (pintype "bidirectional"))
    )
    (net (code "19") (name "/MCU_DATA_P") (class "Default")
      (node (ref "J1") (pin "9") (pintype "passive"))
      (node (ref "U6") (pin "22") (pinfunction "PA12_22") (pintype "bidirectional"))
    )
    (net (code "20") (name "/PMS_SCL") (class "Default")
      (node (ref "J1") (pin "16") (pintype "passive"))
      (node (ref "R16") (pin "1") (pinfunction "1_1") (pintype "passive"))
      (node (ref "U1") (pin "5") (pinfunction "SCL_5") (pintype "input"))
      (node (ref "U4") (pin "7") (pinfunction "SCL_7") (pintype "input"))
      (node (ref "U6") (pin "25") (pinfunction "PA15_25") (pintype "bidirectional"))
    )
    (net (code "21") (name "/PMS_SDA") (class "Default")
      (node (ref "J1") (pin "15") (pintype "passive"))
      (node (ref "R15") (pin "1") (pinfunction "1_1") (pintype "passive"))
      (node (ref "U1") (pin "6") (pinfunction "SDA_6") (pintype "bidirectional"))
      (node (ref "U4") (pin "8") (pinfunction "SDA_8") (pintype "bidirectional"))
      (node (ref "U6") (pin "30") (pinfunction "PB7_30") (pintype "bidirectional"))
    )
    (net (code "22") (name "/PWR_BTN_N") (class "Default")
      (node (ref "S1") (pin "2") (pinfunction "2_2") (pintype "passive"))
      (node (ref "U6") (pin "7") (pinfunction "PA2_7") (pintype "bidirectional"))
    )
    (net (code "23") (name "/PWR_ON") (class "Default")
      (node (ref "J1") (pin "19") (pintype "passive"))
      (node (ref "U2") (pin "13") (pinfunction "EN_13") (pintype "input"))
      (node (ref "U3") (pin "13") (pinfunction "EN_13") (pintype "input"))
      (node (ref "U5") (pin "13") (pinfunction "EN_13") (pintype "input"))
      (node (ref "U6") (pin "12") (pinfunction "PA7_12") (pintype "bidirectional"))
      (node (ref "U7") (pin "13") (pinfunction "EN_13") (pintype "input"))
      (node (ref "U8") (pin "9") (pinfunction "EN_9") (pintype "input"))
    )
    (net (code "24") (name "/RESET_N") (class "Default")
      (node (ref "C36") (pin "2") (pinfunction "2_2") (pintype "passive"))
      (node (ref "J3") (pin "3") (pinfunction "3_3") (pintype "passive"))
      (node (ref "S2") (pin "1") (pinfunction "1_1") (pintype "passive"))
      (node (ref "U6") (pin "4") (pinfunction "PG10-NRST_4") (pintype "bidirectional"))
    )
    (net (code "25") (name "/SS_1V0") (class "Default")
      (node (ref "C35") (pin "2") (pinfunction "2_2") (pintype "passive"))
      (node (ref "U7") (pin "9") (pinfunction "SS/TR_9") (pintype "input"))
    )
    (net (code "26") (name "/SS_1V8") (class "Default")
      (node (ref "C21") (pin "2") (pinfunction "2_2") (pintype "passive"))
      (node (ref "U3") (pin "9") (pinfunction "SS/TR_9") (pintype "input"))
    )
    (net (code "27") (name "/SS_1V15") (class "Default")
      (node (ref "C31") (pin "2") (pinfunction "2_2") (pintype "passive"))
      (node (ref "U5") (pin "9") (pinfunction "SS/TR_9") (pintype "input"))
    )
    (net (code "28") (name "/SS_3V3") (class "Default")
      (node (ref "C13") (pin "2") (pinfunction "2_2") (pintype "passive"))
      (node (ref "U2") (pin "9") (pinfunction "SS/TR_9") (pintype "input"))
    )
    (net (code "29") (name "/SS_5V0") (class "Default")
      (node (ref "C41") (pin "2") (pinfunction "2_2") (pintype "passive"))
      (node (ref "U8") (pin "6") (pinfunction "SS_6") (pintype "input"))
    )
    (net (code "30") (name "/STUSB_INT") (class "Default")
      (node (ref "J1") (pin "20") (pintype "passive+no_connect"))
    )
    (net (code "31") (name "/SWCLK") (class "Default")
      (node (ref "J3") (pin "4") (pinfunction "4_4") (pintype "passive"))
      (node (ref "U6") (pin "24") (pinfunction "PA14_24") (pintype "bidirectional"))
    )
    (net (code "32") (name "/SWDIO") (class "Default")
      (node (ref "J3") (pin "2") (pinfunction "2_2") (pintype "passive"))
      (node (ref "U6") (pin "23") (pinfunction "PA13_23") (pintype "bidirectional"))
    )
    (net (code "33") (name "/SWO") (class "Default")
      (node (ref "J3") (pin "6") (pinfunction "6_6") (pintype "passive+no_connect"))
    )
    (net (code "34") (name "/SW_1V0") (class "Default")
      (node (ref "L5") (pin "1") (pinfunction "1_1") (pintype "passive"))
      (node (ref "U7") (pin "1") (pinfunction "SW_1") (pintype "power_in"))
      (node (ref "U7") (pin "2") (pinfunction "SW_2") (pintype "power_in"))
      (node (ref "U7") (pin "3") (pinfunction "SW_3") (pintype "power_in"))
    )
    (net (code "35") (name "/SW_1V8") (class "Default")
      (node (ref "L3") (pin "1") (pinfunction "1_1") (pintype "passive"))
      (node (ref "U3") (pin "1") (pinfunction "SW_1") (pintype "power_in"))
      (node (ref "U3") (pin "2") (pinfunction "SW_2") (pintype "power_in"))
      (node (ref "U3") (pin "3") (pinfunction "SW_3") (pintype "power_in"))
    )
    (net (code "36") (name "/SW_1V15") (class "Default")
      (node (ref "L4") (pin "1") (pinfunction "1_1") (pintype "passive"))
      (node (ref "U5") (pin "1") (pinfunction "SW_1") (pintype "power_in"))
      (node (ref "U5") (pin "2") (pinfunction "SW_2") (pintype "power_in"))
      (node (ref "U5") (pin "3") (pinfunction "SW_3") (pintype "power_in"))
    )
    (net (code "37") (name "/SW_3V3") (class "Default")
      (node (ref "L2") (pin "1") (pinfunction "1_1") (pintype "passive"))
      (node (ref "U2") (pin "1") (pinfunction "SW_1") (pintype "power_in"))
      (node (ref "U2") (pin "2") (pinfunction "SW_2") (pintype "power_in"))
      (node (ref "U2") (pin "3") (pinfunction "SW_3") (pintype "power_in"))
    )
    (net (code "38") (name "/SW_5V0") (class "Default")
      (node (ref "L6") (pin "2") (pinfunction "2_2") (pintype "passive"))
      (node (ref "U8") (pin "1") (pinfunction "SW_1") (pintype "power_in"))
      (node (ref "U8") (pin "2") (pinfunction "SW_2") (pintype "power_in"))
    )
    (net (code "39") (name "/SYS_SCL") (class "Default")
      (node (ref "J2") (pin "9") (pinfunction "9_9") (pintype "passive"))
      (node (ref "R20") (pin "1") (pinfunction "1_1") (pintype "passive"))
      (node (ref "U6") (pin "19") (pinfunction "PA9_19") (pintype "bidirectional"))
    )
    (net (code "40") (name "/SYS_SDA") (class "Default")
      (node (ref "J2") (pin "8") (pinfunction "8_8") (pintype "passive"))
      (node (ref "R19") (pin "1") (pinfunction "1_1") (pintype "passive"))
      (node (ref "U6") (pin "2") (pinfunction "PF0-OSC_IN_2") (pintype "input"))
    )
    (net (code "41") (name "/TEMP") (class "Default")
      (node (ref "J4") (pin "15") (pintype "passive"))
      (node (ref "R22") (pin "1") (pinfunction "1_1") (pintype "passive"))
      (node (ref "U6") (pin "11") (pinfunction "PA6_11") (pintype "bidirectional"))
    )
    (net (code "42") (name "/VOL_DOWN_N") (class "Default")
      (node (ref "J2") (pin "4") (pinfunction "4_4") (pintype "passive"))
      (node (ref "U6") (pin "26") (pinfunction "PB3_26") (pintype "bidirectional"))
    )
    (net (code "43") (name "/VOL_UP_N") (class "Default")
      (node (ref "J2") (pin "3") (pinfunction "3_3") (pintype "passive"))
      (node (ref "U6") (pin "27") (pinfunction "PB4_27") (pintype "bidirectional"))
    )
    (net (code "44") (name "/WII_DATA_N") (class "Default")
      (node (ref "J1") (pin "12") (pintype "passive"))
      (node (ref "J4") (pin "5") (pintype "passive"))
    )
    (net (code "45") (name "/WII_DATA_P") (class "Default")
      (node (ref "J1") (pin "10") (pintype "passive"))
      (node (ref "J4") (pin "6") (pintype "passive"))
    )
    (net (code "46") (name "/WII_SCL") (class "Default")
      (node (ref "Q1") (pin "6") (pinfunction "D1_6") (pintype "passive"))
      (node (ref "R18") (pin "1") (pinfunction "1_1") (pintype "passive"))
      (node (ref "U6") (pin "18") (pinfunction "PA8_18") (pintype "bidirectional"))
    )
    (net (code "47") (name "/WII_SCL_1V8") (class "Default")
      (node (ref "J2") (pin "12") (pinfunction "12_12") (pintype "passive"))
      (node (ref "Q1") (pin "1") (pinfunction "S1_1") (pintype "passive"))
    )
    (net (code "48") (name "/WII_SDA") (class "Default")
      (node (ref "Q1") (pin "3") (pinfunction "D2_3") (pintype "passive"))
      (node (ref "R17") (pin "1") (pinfunction "1_1") (pintype "passive"))
      (node (ref "U6") (pin "28") (pinfunction "PB5_28") (pintype "bidirectional"))
    )
    (net (code "49") (name "/WII_SDA_1V8") (class "Default")
      (node (ref "J2") (pin "11") (pinfunction "11_11") (pintype "passive"))
      (node (ref "Q1") (pin "4") (pinfunction "S2_4") (pintype "passive"))
    )
    (net (code "50") (name "1V0") (class "Default")
      (node (ref "C34") (pin "2") (pinfunction "2_2") (pintype "passive"))
      (node (ref "J4") (pin "11") (pintype "passive"))
      (node (ref "J4") (pin "12") (pintype "passive"))
      (node (ref "J4") (pin "8") (pintype "passive"))
      (node (ref "J4") (pin "9") (pintype "passive"))
      (node (ref "L5") (pin "2") (pinfunction "2_2") (pintype "passive"))
      (node (ref "R12") (pin "2") (pinfunction "2_2") (pintype "passive"))
      (node (ref "U7") (pin "14") (pinfunction "VOS_14") (pintype "input"))
    )
    (net (code "51") (name "1V8") (class "Default")
      (node (ref "C20") (pin "2") (pinfunction "2_2") (pintype "passive"))
      (node (ref "J4") (pin "1") (pintype "passive"))
      (node (ref "L3") (pin "2") (pinfunction "2_2") (pintype "passive"))
      (node (ref "Q1") (pin "2") (pinfunction "G1_2") (pintype "passive"))
      (node (ref "Q1") (pin "5") (pinfunction "G2_5") (pintype "passive"))
      (node (ref "R8") (pin "2") (pinfunction "2_2") (pintype "passive"))
      (node (ref "U3") (pin "14") (pinfunction "VOS_14") (pintype "input"))
    )
    (net (code "52") (name "1V15") (class "Default")
      (node (ref "C30") (pin "2") (pinfunction "2_2") (pintype "passive"))
      (node (ref "J4") (pin "17") (pintype "passive"))
      (node (ref "J4") (pin "18") (pintype "passive"))
      (node (ref "J4") (pin "19") (pintype "passive"))
      (node (ref "L4") (pin "2") (pinfunction "2_2") (pintype "passive"))
      (node (ref "R10") (pin "2") (pinfunction "2_2") (pintype "passive"))
      (node (ref "U5") (pin "14") (pinfunction "VOS_14") (pintype "input"))
    )
    (net (code "53") (name "3V3") (class "Default")
      (node (ref "C12") (pin "2") (pinfunction "2_2") (pintype "passive"))
      (node (ref "C4") (pin "2") (pinfunction "2_2") (pintype "passive"))
      (node (ref "J2") (pin "15") (pinfunction "15_15") (pintype "passive"))
      (node (ref "J2") (pin "16") (pinfunction "16_16") (pintype "passive"))
      (node (ref "J4") (pin "3") (pintype "passive"))
      (node (ref "L2") (pin "2") (pinfunction "2_2") (pintype "passive"))
      (node (ref "R19") (pin "2") (pinfunction "2_2") (pintype "passive"))
      (node (ref "R20") (pin "2") (pinfunction "2_2") (pintype "passive"))
      (node (ref "R3") (pin "2") (pinfunction "2_2") (pintype "passive"))
      (node (ref "U2") (pin "14") (pinfunction "VOS_14") (pintype "input"))
    )
    (net (code "54") (name "3V3_AO") (class "Default")
      (node (ref "C2") (pin "2") (pinfunction "2_2") (pintype "passive"))
      (node (ref "C22") (pin "2") (pinfunction "2_2") (pintype "passive"))
      (node (ref "C23") (pin "2") (pinfunction "2_2") (pintype "passive"))
      (node (ref "C24") (pin "2") (pinfunction "2_2") (pintype "passive"))
      (node (ref "C25") (pin "2") (pinfunction "2_2") (pintype "passive"))
      (node (ref "C26") (pin "2") (pinfunction "2_2") (pintype "passive"))
      (node (ref "C43") (pin "2") (pinfunction "2_2") (pintype "passive"))
      (node (ref "C5") (pin "2") (pinfunction "2_2") (pintype "passive"))
      (node (ref "J1") (pin "5") (pintype "passive"))
      (node (ref "J2") (pin "14") (pinfunction "14_14") (pintype "passive"))
      (node (ref "J3") (pin "1") (pinfunction "1_1") (pintype "passive"))
      (node (ref "J4") (pin "14") (pintype "passive"))
      (node (ref "R15") (pin "2") (pinfunction "2_2") (pintype "passive"))
      (node (ref "R16") (pin "2") (pinfunction "2_2") (pintype "passive"))
      (node (ref "R17") (pin "2") (pinfunction "2_2") (pintype "passive"))
      (node (ref "R18") (pin "2") (pinfunction "2_2") (pintype "passive"))
      (node (ref "U6") (pin "1") (pinfunction "VDD_1") (pintype "power_in"))
      (node (ref "U6") (pin "15") (pinfunction "VDDA_15") (pintype "power_in"))
      (node (ref "U6") (pin "17") (pinfunction "VDD_17") (pintype "power_in"))
      (node (ref "U9") (pin "5") (pinfunction "OUT_5") (pintype "power_in"))
    )
    (net (code "55") (name "5V0") (class "Default")
      (node (ref "C1") (pin "2") (pinfunction "2_2") (pintype "passive"))
      (node (ref "C3") (pin "2") (pinfunction "2_2") (pintype "passive"))
      (node (ref "C38") (pin "2") (pinfunction "2_2") (pintype "passive"))
      (node (ref "C39") (pin "2") (pinfunction "2_2") (pintype "passive"))
      (node (ref "C40") (pin "2") (pinfunction "2_2") (pintype "passive"))
      (node (ref "J1") (pin "1") (pintype "passive"))
      (node (ref "J1") (pin "3") (pintype "passive"))
      (node (ref "J2") (pin "17") (pinfunction "17_17") (pintype "passive"))
      (node (ref "J2") (pin "18") (pinfunction "18_18") (pintype "passive"))
      (node (ref "U8") (pin "3") (pinfunction "VOUT_3") (pintype "power_in"))
      (node (ref "U8") (pin "4") (pinfunction "VOUT_4") (pintype "power_in"))
      (node (ref "U8") (pin "7") (pinfunction "FB_7") (pintype "input"))
    )
    (net (code "56") (name "GND") (class "Default")
      (node (ref "C1") (pin "1") (pinfunction "1_1") (pintype "passive"))
      (node (ref "C10") (pin "1") (pinfunction "1_1") (pintype "passive"))
      (node (ref "C11") (pin "1") (pinfunction "1_1") (pintype "passive"))
      (node (ref "C12") (pin "1") (pinfunction "1_1") (pintype "passive"))
      (node (ref "C13") (pin "1") (pinfunction "1_1") (pintype "passive"))
      (node (ref "C15") (pin "1") (pinfunction "1_1") (pintype "passive"))
      (node (ref "C16") (pin "2") (pinfunction "2_2") (pintype "passive"))
      (node (ref "C17") (pin "2") (pinfunction "2_2") (pintype "passive"))
      (node (ref "C18") (pin "1") (pinfunction "1_1") (pintype "passive"))
      (node (ref "C19") (pin "1") (pinfunction "1_1") (pintype "passive"))
      (node (ref "C2") (pin "1") (pinfunction "1_1") (pintype "passive"))
      (node (ref "C20") (pin "1") (pinfunction "1_1") (pintype "passive"))
      (node (ref "C21") (pin "1") (pinfunction "1_1") (pintype "passive"))
      (node (ref "C22") (pin "1") (pinfunction "1_1") (pintype "passive"))
      (node (ref "C23") (pin "1") (pinfunction "1_1") (pintype "passive"))
      (node (ref "C24") (pin "1") (pinfunction "1_1") (pintype "passive"))
      (node (ref "C25") (pin "1") (pinfunction "1_1") (pintype "passive"))
      (node (ref "C26") (pin "1") (pinfunction "1_1") (pintype "passive"))
      (node (ref "C27") (pin "1") (pinfunction "1_1") (pintype "passive"))
      (node (ref "C28") (pin "1") (pinfunction "1_1") (pintype "passive"))
      (node (ref "C29") (pin "1") (pinfunction "1_1") (pintype "passive"))
      (node (ref "C3") (pin "1") (pinfunction "1_1") (pintype "passive"))
      (node (ref "C30") (pin "1") (pinfunction "1_1") (pintype "passive"))
      (node (ref "C31") (pin "1") (pinfunction "1_1") (pintype "passive"))
      (node (ref "C32") (pin "1") (pinfunction "1_1") (pintype "passive"))
      (node (ref "C33") (pin "1") (pinfunction "1_1") (pintype "passive"))
      (node (ref "C34") (pin "1") (pinfunction "1_1") (pintype "passive"))
      (node (ref "C35") (pin "1") (pinfunction "1_1") (pintype "passive"))
      (node (ref "C36") (pin "1") (pinfunction "1_1") (pintype "passive"))
      (node (ref "C37") (pin "1") (pinfunction "1_1") (pintype "passive"))
      (node (ref "C38") (pin "1") (pinfunction "1_1") (pintype "passive"))
      (node (ref "C39") (pin "1") (pinfunction "1_1") (pintype "passive"))
      (node (ref "C4") (pin "1") (pinfunction "1_1") (pintype "passive"))
      (node (ref "C40") (pin "1") (pinfunction "1_1") (pintype "passive"))
      (node (ref "C41") (pin "1") (pinfunction "1_1") (pintype "passive"))
      (node (ref "C42") (pin "1") (pinfunction "1_1") (pintype "passive"))
      (node (ref "C43") (pin "1") (pinfunction "1_1") (pintype "passive"))
      (node (ref "C44") (pin "1") (pinfunction "1_1") (pintype "passive"))
      (node (ref "C5") (pin "1") (pinfunction "1_1") (pintype "passive"))
      (node (ref "C6") (pin "1") (pinfunction "1_1") (pintype "passive"))
      (node (ref "C7") (pin "1") (pinfunction "1_1") (pintype "passive"))
      (node (ref "C8") (pin "1") (pinfunction "1_1") (pintype "passive"))
      (node (ref "C9") (pin "1") (pinfunction "1_1") (pintype "passive"))
      (node (ref "J1") (pin "13") (pintype "passive"))
      (node (ref "J1") (pin "14") (pintype "passive"))
      (node (ref "J1") (pin "7") (pintype "passive"))
      (node (ref "J1") (pin "8") (pintype "passive"))
      (node (ref "J1") (pin "SHIELD") (pintype "passive"))
      (node (ref "J2") (pin "10") (pinfunction "10_10") (pintype "passive"))
      (node (ref "J2") (pin "13") (pinfunction "13_13") (pintype "passive"))
      (node (ref "J2") (pin "5") (pinfunction "5_5") (pintype "passive"))
      (node (ref "J2") (pin "7") (pinfunction "7_7") (pintype "passive"))
      (node (ref "J2") (pin "SHIELD") (pinfunction "SHIELD_SHIELD") (pintype "passive"))
      (node (ref "J3") (pin "5") (pinfunction "5_5") (pintype "passive"))
      (node (ref "J4") (pin "10") (pintype "passive"))
      (node (ref "J4") (pin "13") (pintype "passive"))
      (node (ref "J4") (pin "16") (pintype "passive"))
      (node (ref "J4") (pin "2") (pintype "passive"))
      (node (ref "J4") (pin "20") (pintype "passive"))
      (node (ref "J4") (pin "4") (pintype "passive"))
      (node (ref "J4") (pin "7") (pintype "passive"))
      (node (ref "J5") (pin "4") (pinfunction "4_4") (pintype "passive"))
      (node (ref "J5") (pin "SHIELD") (pinfunction "SHIELD_SHIELD") (pintype "passive"))
      (node (ref "R11") (pin "1") (pinfunction "1_1") (pintype "passive"))
      (node (ref "R13") (pin "1") (pinfunction "1_1") (pintype "passive"))
      (node (ref "R14") (pin "1") (pinfunction "1_1") (pintype "passive"))
      (node (ref "R2") (pin "2") (pinfunction "2_2") (pintype "passive"))
      (node (ref "R21") (pin "1") (pinfunction "1_1") (pintype "passive"))
      (node (ref "R22") (pin "2") (pinfunction "2_2") (pintype "passive"))
      (node (ref "R4") (pin "1") (pinfunction "1_1") (pintype "passive"))
      (node (ref "R5") (pin "1") (pinfunction "1_1") (pintype "passive"))
      (node (ref "R6") (pin "1") (pinfunction "1_1") (pintype "passive"))
      (node (ref "R7") (pin "1") (pinfunction "1_1") (pintype "passive"))
      (node (ref "R9") (pin "1") (pinfunction "1_1") (pintype "passive"))
      (node (ref "S1") (pin "1") (pinfunction "1_1") (pintype "passive"))
      (node (ref "S2") (pin "2") (pinfunction "2_2") (pintype "passive"))
      (node (ref "TP7") (pin "1") (pintype "passive"))
      (node (ref "U1") (pin "17") (pinfunction "PGND_17") (pintype "power_in"))
      (node (ref "U1") (pin "18") (pinfunction "PGND_18") (pintype "power_in"))
      (node (ref "U1") (pin "2") (pinfunction "PSEL_2") (pintype "input"))
      (node (ref "U1") (pin "25") (pinfunction "EP_25") (pintype "passive"))
      (node (ref "U2") (pin "15") (pinfunction "PGND_15") (pintype "power_in"))
      (node (ref "U2") (pin "16") (pinfunction "PGND_16") (pintype "power_in"))
      (node (ref "U2") (pin "17") (pinfunction "EP_17") (pintype "passive"))
      (node (ref "U2") (pin "6") (pinfunction "AGND_6") (pintype "power_in"))
      (node (ref "U2") (pin "7") (pinfunction "FSW_7") (pintype "input"))
      (node (ref "U2") (pin "8") (pinfunction "DEF_8") (pintype "input"))
      (node (ref "U3") (pin "15") (pinfunction "PGND_15") (pintype "power_in"))
      (node (ref "U3") (pin "16") (pinfunction "PGND_16") (pintype "power_in"))
      (node (ref "U3") (pin "17") (pinfunction "EP_17") (pintype "passive"))
      (node (ref "U3") (pin "6") (pinfunction "AGND_6") (pintype "power_in"))
      (node (ref "U3") (pin "7") (pinfunction "FSW_7") (pintype "input"))
      (node (ref "U3") (pin "8") (pinfunction "DEF_8") (pintype "input"))
      (node (ref "U4") (pin "1") (pinfunction "CTG_1") (pintype "power_in"))
      (node (ref "U4") (pin "4") (pinfunction "GND_4") (pintype "power_in"))
      (node (ref "U4") (pin "6") (pinfunction "QSTRT_6") (pintype "input"))
      (node (ref "U4") (pin "9") (pinfunction "EP_9") (pintype "passive"))
      (node (ref "U5") (pin "15") (pinfunction "PGND_15") (pintype "power_in"))
      (node (ref "U5") (pin "16") (pinfunction "PGND_16") (pintype "power_in"))
      (node (ref "U5") (pin "17") (pinfunction "EP_17") (pintype "passive"))
      (node (ref "U5") (pin "6") (pinfunction "AGND_6") (pintype "power_in"))
      (node (ref "U5") (pin "7") (pinfunction "FSW_7") (pintype "input"))
      (node (ref "U5") (pin "8") (pinfunction "DEF_8") (pintype "input"))
      (node (ref "U6") (pin "14") (pinfunction "VSSA_14") (pintype "power_in"))
      (node (ref "U6") (pin "16") (pinfunction "VSS_16") (pintype "power_in"))
      (node (ref "U6") (pin "32") (pinfunction "VSS_32") (pintype "power_in"))
      (node (ref "U6") (pin "33") (pinfunction "EP_33") (pintype "passive"))
      (node (ref "U7") (pin "15") (pinfunction "PGND_15") (pintype "power_in"))
      (node (ref "U7") (pin "16") (pinfunction "PGND_16") (pintype "power_in"))
      (node (ref "U7") (pin "17") (pinfunction "EP_17") (pintype "passive"))
      (node (ref "U7") (pin "6") (pinfunction "AGND_6") (pintype "power_in"))
      (node (ref "U7") (pin "7") (pinfunction "FSW_7") (pintype "input"))
      (node (ref "U7") (pin "8") (pinfunction "DEF_8") (pintype "input"))
      (node (ref "U8") (pin "11") (pinfunction "GND_11") (pintype "power_in"))
      (node (ref "U9") (pin "2") (pinfunction "GND_2") (pintype "power_in"))
    )
    (net (code "57") (name "Net-(U1-CE)") (class "Default")
      (node (ref "R6") (pin "2") (pinfunction "2_2") (pintype "passive"))
      (node (ref "U1") (pin "9") (pinfunction "CE_9") (pintype "input"))
    )
    (net (code "58") (name "Net-(U1-ILIM)") (class "Default")
      (node (ref "R7") (pin "2") (pinfunction "2_2") (pintype "passive"))
      (node (ref "U1") (pin "10") (pinfunction "ILIM_10") (pintype "input"))
    )
    (net (code "59") (name "Net-(U1-OTG)") (class "Default")
      (node (ref "R5") (pin "2") (pinfunction "2_2") (pintype "passive"))
      (node (ref "U1") (pin "8") (pinfunction "OTG_8") (pintype "input"))
    )
    (net (code "60") (name "VBAT") (class "Default")
      (node (ref "C15") (pin "2") (pinfunction "2_2") (pintype "passive"))
      (node (ref "C27") (pin "2") (pinfunction "2_2") (pintype "passive"))
      (node (ref "TP6") (pin "1") (pintype "passive"))
      (node (ref "U1") (pin "13") (pinfunction "BAT_13") (pintype "power_in"))
      (node (ref "U1") (pin "14") (pinfunction "BAT_14") (pintype "power_in"))
      (node (ref "U4") (pin "2") (pinfunction "CELL_2") (pintype "power_in"))
      (node (ref "U4") (pin "3") (pinfunction "VDD_3") (pintype "power_in"))
    )
    (net (code "61") (name "VCHRG") (class "Default")
      (node (ref "C44") (pin "2") (pinfunction "2_2") (pintype "passive"))
      (node (ref "C6") (pin "2") (pinfunction "2_2") (pintype "passive"))
      (node (ref "J1") (pin "2") (pintype "passive"))
      (node (ref "J1") (pin "4") (pintype "passive"))
      (node (ref "J1") (pin "6") (pintype "passive"))
      (node (ref "U1") (pin "1") (pinfunction "VBUS_1") (pintype "power_in"))
      (node (ref "U1") (pin "24") (pinfunction "VBUS_24") (pintype "power_in"))
    )
    (net (code "62") (name "VSYS") (class "Default")
      (node (ref "C10") (pin "2") (pinfunction "2_2") (pintype "passive"))
      (node (ref "C11") (pin "2") (pinfunction "2_2") (pintype "passive"))
      (node (ref "C18") (pin "2") (pinfunction "2_2") (pintype "passive"))
      (node (ref "C19") (pin "2") (pinfunction "2_2") (pintype "passive"))
      (node (ref "C28") (pin "2") (pinfunction "2_2") (pintype "passive"))
      (node (ref "C29") (pin "2") (pinfunction "2_2") (pintype "passive"))
      (node (ref "C32") (pin "2") (pinfunction "2_2") (pintype "passive"))
      (node (ref "C33") (pin "2") (pinfunction "2_2") (pintype "passive"))
      (node (ref "C37") (pin "2") (pinfunction "2_2") (pintype "passive"))
      (node (ref "C42") (pin "2") (pinfunction "2_2") (pintype "passive"))
      (node (ref "C7") (pin "2") (pinfunction "2_2") (pintype "passive"))
      (node (ref "C8") (pin "2") (pinfunction "2_2") (pintype "passive"))
      (node (ref "C9") (pin "2") (pinfunction "2_2") (pintype "passive"))
      (node (ref "L1") (pin "2") (pinfunction "2_2") (pintype "passive"))
      (node (ref "L6") (pin "1") (pinfunction "1_1") (pintype "passive"))
      (node (ref "U1") (pin "15") (pinfunction "SYS_15") (pintype "power_in"))
      (node (ref "U1") (pin "16") (pinfunction "SYS_16") (pintype "power_in"))
      (node (ref "U2") (pin "10") (pinfunction "AVIN_10") (pintype "power_in"))
      (node (ref "U2") (pin "11") (pinfunction "PVIN_11") (pintype "power_in"))
      (node (ref "U2") (pin "12") (pinfunction "PVIN_12") (pintype "power_in"))
      (node (ref "U3") (pin "10") (pinfunction "AVIN_10") (pintype "power_in"))
      (node (ref "U3") (pin "11") (pinfunction "PVIN_11") (pintype "power_in"))
      (node (ref "U3") (pin "12") (pinfunction "PVIN_12") (pintype "power_in"))
      (node (ref "U5") (pin "10") (pinfunction "AVIN_10") (pintype "power_in"))
      (node (ref "U5") (pin "11") (pinfunction "PVIN_11") (pintype "power_in"))
      (node (ref "U5") (pin "12") (pinfunction "PVIN_12") (pintype "power_in"))
      (node (ref "U7") (pin "10") (pinfunction "AVIN_10") (pintype "power_in"))
      (node (ref "U7") (pin "11") (pinfunction "PVIN_11") (pintype "power_in"))
      (node (ref "U7") (pin "12") (pinfunction "PVIN_12") (pintype "power_in"))
      (node (ref "U8") (pin "10") (pinfunction "VIN_10") (pintype "power_in"))
      (node (ref "U9") (pin "1") (pinfunction "IN_1") (pintype "power_in"))
      (node (ref "U9") (pin "3") (pinfunction "EN_3") (pintype "input"))
    )
    (net (code "63") (name "unconnected-(J5-Pad1)") (class "Default")
      (node (ref "J5") (pin "1") (pinfunction "1_1") (pintype "passive+no_connect"))
    )
    (net (code "64") (name "unconnected-(U1-PG-Pad3)") (class "Default")
      (node (ref "U1") (pin "3") (pinfunction "PG_3") (pintype "output+no_connect"))
    )
    (net (code "65") (name "unconnected-(U1-STAT-Pad4)") (class "Default")
      (node (ref "U1") (pin "4") (pinfunction "STAT_4") (pintype "output+no_connect"))
    )
    (net (code "66") (name "unconnected-(U2-PG-Pad4)") (class "Default")
      (node (ref "U2") (pin "4") (pinfunction "PG_4") (pintype "output+no_connect"))
    )
    (net (code "67") (name "unconnected-(U3-PG-Pad4)") (class "Default")
      (node (ref "U3") (pin "4") (pinfunction "PG_4") (pintype "output+no_connect"))
    )
    (net (code "68") (name "unconnected-(U5-PG-Pad4)") (class "Default")
      (node (ref "U5") (pin "4") (pinfunction "PG_4") (pintype "output+no_connect"))
    )
    (net (code "69") (name "unconnected-(U6-PA1-Pad6)") (class "Default")
      (node (ref "U6") (pin "6") (pinfunction "PA1_6") (pintype "bidirectional+no_connect"))
    )
    (net (code "70") (name "unconnected-(U6-PA3-Pad8)") (class "Default")
      (node (ref "U6") (pin "8") (pinfunction "PA3_8") (pintype "bidirectional+no_connect"))
    )
    (net (code "71") (name "unconnected-(U6-PA4-Pad9)") (class "Default")
      (node (ref "U6") (pin "9") (pinfunction "PA4_9") (pintype "bidirectional+no_connect"))
    )
    (net (code "72") (name "unconnected-(U6-PB0-Pad13)") (class "Default")
      (node (ref "U6") (pin "13") (pinfunction "PB0_13") (pintype "bidirectional+no_connect"))
    )
    (net (code "73") (name "unconnected-(U7-PG-Pad4)") (class "Default")
      (node (ref "U7") (pin "4") (pinfunction "PG_4") (pintype "output+no_connect"))
    )
    (net (code "74") (name "unconnected-(U8-HYS-Pad8)") (class "Default")
      (node (ref "U8") (pin "8") (pinfunction "HYS_8") (pintype "output+no_connect"))
    )
    (net (code "75") (name "unconnected-(U8-PG-Pad5)") (class "Default")
      (node (ref "U8") (pin "5") (pinfunction "PG_5") (pintype "output+no_connect"))
    )
    (net (code "76") (name "unconnected-(U9-NC-Pad4)") (class "Default")
      (node (ref "U9") (pin "4") (pinfunction "NC_4") (pintype "passive+no_connect"))
    )
  )
)
